# Cing_bot.net
KiCad netlist of a schematic drawn in EAGLE
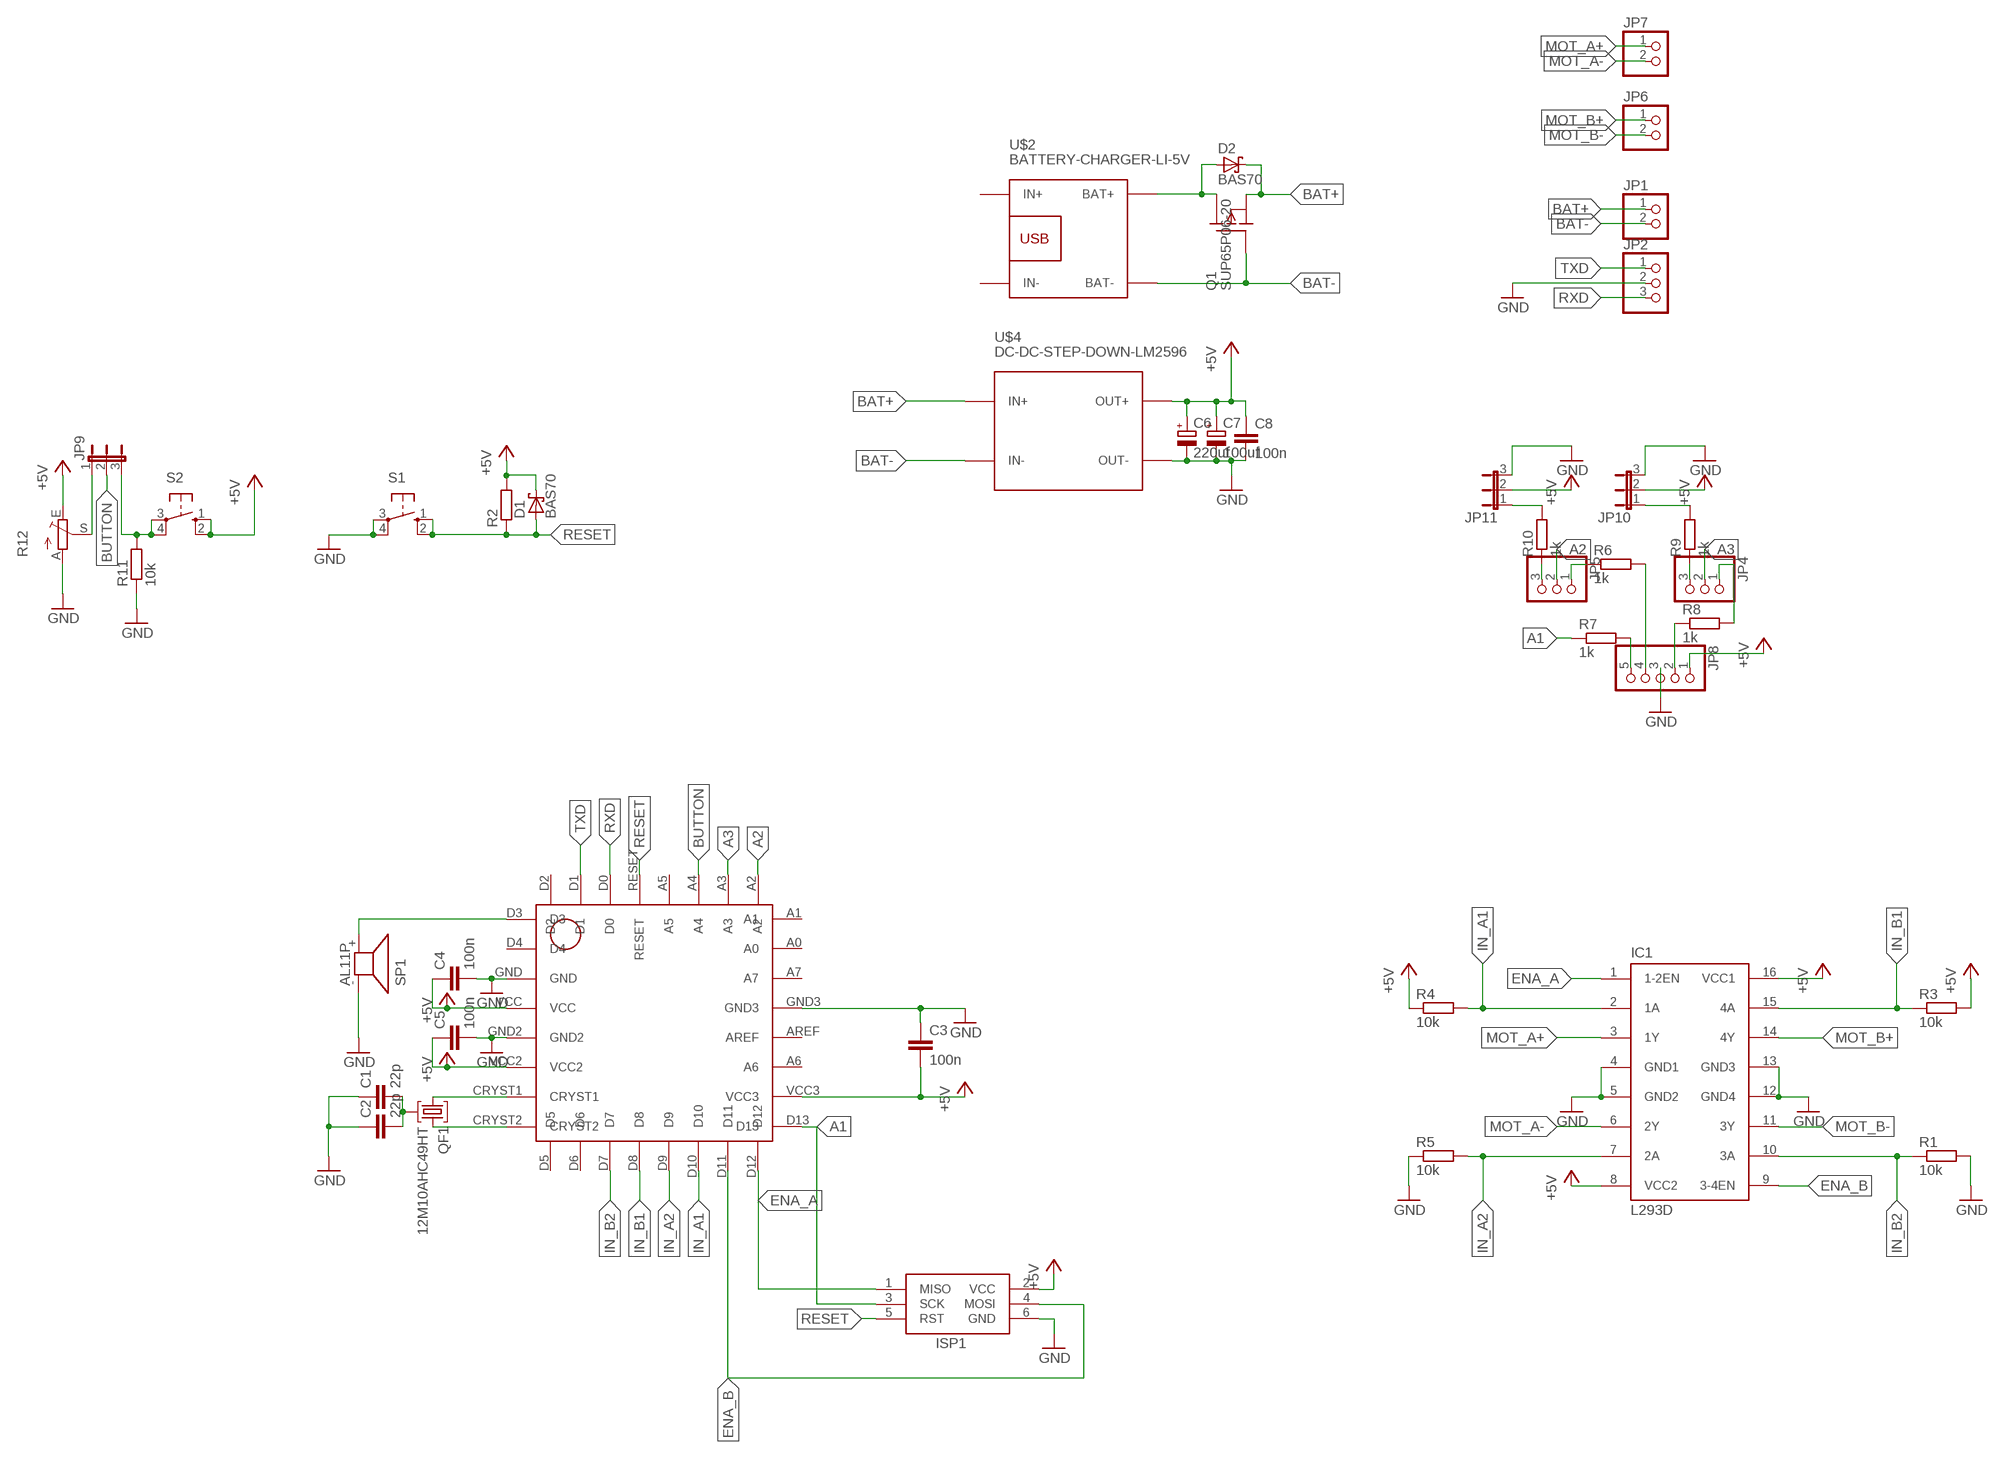
[diagram p0: schematic, sheet 1]

(export (version "E")
  (design (tool "Eeschema 10.0.6"))
  (components
    (comp (ref "C1")
      (value "22p")
      (footprint "eagle-import:C1206")
      (libsource (lib "eagle-import") (part "C-EUC1206"))
    )
    (comp (ref "C2")
      (value "22p")
      (footprint "eagle-import:C1206")
      (libsource (lib "eagle-import") (part "C-EUC1206"))
    )
    (comp (ref "C3")
      (value "100n")
      (footprint "eagle-import:C1206")
      (libsource (lib "eagle-import") (part "C-EUC1206"))
    )
    (comp (ref "C4")
      (value "100n")
      (footprint "eagle-import:C1206")
      (libsource (lib "eagle-import") (part "C-EUC1206"))
    )
    (comp (ref "C5")
      (value "100n")
      (footprint "eagle-import:C1206")
      (libsource (lib "eagle-import") (part "C-EUC1206"))
    )
    (comp (ref "C6")
      (value "220uf")
      (footprint "eagle-import:E3,5-8")
      (libsource (lib "eagle-import") (part "CPOL-EUE3.5-8"))
    )
    (comp (ref "C7")
      (value "100uf")
      (footprint "eagle-import:E3,5-8")
      (libsource (lib "eagle-import") (part "CPOL-EUE3.5-8"))
    )
    (comp (ref "C8")
      (value "100n")
      (footprint "eagle-import:C1206")
      (libsource (lib "eagle-import") (part "C-EUC1206"))
    )
    (comp (ref "D1")
      (value "BAS70")
      (footprint "eagle-import:SOT23")
      (libsource (lib "eagle-import") (part "BAS70"))
    )
    (comp (ref "D2")
      (value "BAS70")
      (footprint "eagle-import:SOT23")
      (libsource (lib "eagle-import") (part "BAS70"))
    )
    (comp (ref "IC1")
      (value "L293D")
      (footprint "eagle-import:DIL16")
      (libsource (lib "eagle-import") (part "L293D"))
    )
    (comp (ref "ISP1")
      (value "AVRISP-6")
      (footprint "eagle-import:AVRISP")
      (libsource (lib "eagle-import") (part "AVRISP-6"))
    )
    (comp (ref "JP1")
      (value "PINHD-1X2")
      (footprint "eagle-import:1X02")
      (libsource (lib "eagle-import") (part "PINHD-1X2"))
    )
    (comp (ref "JP2")
      (value "PINHD-1X3")
      (footprint "eagle-import:1X03")
      (libsource (lib "eagle-import") (part "PINHD-1X3"))
    )
    (comp (ref "JP4")
      (value "PINHD-1X3")
      (footprint "eagle-import:1X03")
      (libsource (lib "eagle-import") (part "PINHD-1X3"))
    )
    (comp (ref "JP5")
      (value "PINHD-1X3")
      (footprint "eagle-import:1X03")
      (libsource (lib "eagle-import") (part "PINHD-1X3"))
    )
    (comp (ref "JP6")
      (value "PINHD-1X2")
      (footprint "eagle-import:1X02")
      (libsource (lib "eagle-import") (part "PINHD-1X2"))
    )
    (comp (ref "JP7")
      (value "PINHD-1X2")
      (footprint "eagle-import:1X02")
      (libsource (lib "eagle-import") (part "PINHD-1X2"))
    )
    (comp (ref "JP8")
      (value "PINHD-1X5")
      (footprint "eagle-import:1X05")
      (libsource (lib "eagle-import") (part "PINHD-1X5"))
    )
    (comp (ref "JP9")
      (value "JP2E")
      (footprint "eagle-import:JP2")
      (libsource (lib "eagle-import") (part "JP2E"))
    )
    (comp (ref "JP10")
      (value "JP2E")
      (footprint "eagle-import:JP2")
      (libsource (lib "eagle-import") (part "JP2E"))
    )
    (comp (ref "JP11")
      (value "JP2E")
      (footprint "eagle-import:JP2")
      (libsource (lib "eagle-import") (part "JP2E"))
    )
    (comp (ref "Q1")
      (value "SUP65P06-20")
      (footprint "eagle-import:TO220")
      (libsource (lib "eagle-import") (part "SUP65P06-20"))
    )
    (comp (ref "QF1")
      (value "12M10AHC49HT")
      (footprint "eagle-import:HC49U")
      (libsource (lib "eagle-import") (part "12M10AHC49HT"))
    )
    (comp (ref "R1")
      (value "10k")
      (footprint "eagle-import:R1206")
      (libsource (lib "eagle-import") (part "R-EU_R1206"))
    )
    (comp (ref "R2")
      (value "R-EU_R1206")
      (footprint "eagle-import:R1206")
      (libsource (lib "eagle-import") (part "R-EU_R1206"))
    )
    (comp (ref "R3")
      (value "10k")
      (footprint "eagle-import:R1206")
      (libsource (lib "eagle-import") (part "R-EU_R1206"))
    )
    (comp (ref "R4")
      (value "10k")
      (footprint "eagle-import:R1206")
      (libsource (lib "eagle-import") (part "R-EU_R1206"))
    )
    (comp (ref "R5")
      (value "10k")
      (footprint "eagle-import:R1206")
      (libsource (lib "eagle-import") (part "R-EU_R1206"))
    )
    (comp (ref "R6")
      (value "1k")
      (footprint "eagle-import:R1206")
      (libsource (lib "eagle-import") (part "R-EU_R1206"))
    )
    (comp (ref "R7")
      (value "1k")
      (footprint "eagle-import:R1206")
      (libsource (lib "eagle-import") (part "R-EU_R1206"))
    )
    (comp (ref "R8")
      (value "1k")
      (footprint "eagle-import:R1206")
      (libsource (lib "eagle-import") (part "R-EU_R1206"))
    )
    (comp (ref "R9")
      (value "1k")
      (footprint "eagle-import:R1206")
      (libsource (lib "eagle-import") (part "R-EU_R1206"))
    )
    (comp (ref "R10")
      (value "1k")
      (footprint "eagle-import:R1206")
      (libsource (lib "eagle-import") (part "R-EU_R1206"))
    )
    (comp (ref "R11")
      (value "10k")
      (footprint "eagle-import:R1206")
      (libsource (lib "eagle-import") (part "R-EU_R1206"))
    )
    (comp (ref "R12")
      (value "TRIM_EU-CA6V")
      (footprint "eagle-import:CA6V")
      (libsource (lib "eagle-import") (part "TRIM_EU-CA6V"))
    )
    (comp (ref "S1")
      (value "10-XX")
      (footprint "eagle-import:B3F-10XX")
      (fields (field (name "MPN") "B3F-1000"))
      (libsource (lib "eagle-import") (part "10-XX"))
    )
    (comp (ref "S2")
      (value "10-XX")
      (footprint "eagle-import:B3F-10XX")
      (fields (field (name "MPN") "B3F-1000"))
      (libsource (lib "eagle-import") (part "10-XX"))
    )
    (comp (ref "SP1")
      (value "AL11P")
      (footprint "eagle-import:AL11P")
      (libsource (lib "eagle-import") (part "AL11P"))
    )
    (comp (ref "U$1")
      (value "PROCESSOR")
      (footprint "eagle-import:PROCESOR")
      (libsource (lib "eagle-import") (part "PROCESSOR"))
    )
    (comp (ref "U$2")
      (value "BATTERY-CHARGER-LI-5V")
      (footprint "eagle-import:BATTERY-CHARGER-LI-5V")
      (libsource (lib "eagle-import") (part "BATTERY-CHARGER-LI-5V"))
    )
    (comp (ref "U$4")
      (value "DC-DC-STEP-DOWN-LM2596")
      (footprint "eagle-import:DC-DC-STEP-DOWN-LM2596")
      (libsource (lib "eagle-import") (part "DC-DC-STEP-DOWN-LM2596"))
    )
  )
  (nets
    (net (code "1") (name "+5V") (class "Default")
      (node (ref "C3") (pin "2") (pinfunction "2_2") (pintype "passive"))
      (node (ref "C4") (pin "1") (pinfunction "1_1") (pintype "passive"))
      (node (ref "C5") (pin "1") (pinfunction "1_1") (pintype "passive"))
      (node (ref "C6") (pin "+") (pinfunction "+_+") (pintype "passive"))
      (node (ref "C7") (pin "+") (pinfunction "+_+") (pintype "passive"))
      (node (ref "C8") (pin "1") (pinfunction "1_1") (pintype "passive"))
      (node (ref "D1") (pin "3") (pinfunction "C_3") (pintype "passive"))
      (node (ref "IC1") (pin "16") (pinfunction "VCC1_16") (pintype "power_in"))
      (node (ref "IC1") (pin "8") (pinfunction "VCC2_8") (pintype "power_in"))
      (node (ref "ISP1") (pin "2") (pinfunction "VCC_2") (pintype "power_in"))
      (node (ref "JP10") (pin "2") (pinfunction "2_2") (pintype "passive"))
      (node (ref "JP11") (pin "2") (pinfunction "2_2") (pintype "passive"))
      (node (ref "JP8") (pin "1") (pinfunction "1_1") (pintype "passive"))
      (node (ref "R12") (pin "E") (pinfunction "E_E") (pintype "passive"))
      (node (ref "R2") (pin "2") (pinfunction "2_2") (pintype "passive"))
      (node (ref "R3") (pin "2") (pinfunction "2_2") (pintype "passive"))
      (node (ref "R4") (pin "1") (pinfunction "1_1") (pintype "passive"))
      (node (ref "S2") (pin "1") (pinfunction "S_1") (pintype "passive"))
      (node (ref "S2") (pin "2") (pinfunction "S1_2") (pintype "passive"))
      (node (ref "U$1") (pin "VCC") (pinfunction "VCC_VCC") (pintype "bidirectional"))
      (node (ref "U$1") (pin "VCC2") (pinfunction "VCC2_VCC2") (pintype "bidirectional"))
      (node (ref "U$1") (pin "VCC3") (pinfunction "VCC3_VCC3") (pintype "bidirectional"))
      (node (ref "U$4") (pin "OUT+") (pinfunction "OUT+_OUT+") (pintype "bidirectional"))
    )
    (net (code "2") (name "A1") (class "Default")
      (node (ref "ISP1") (pin "3") (pinfunction "SCK_3") (pintype "output"))
      (node (ref "R7") (pin "1") (pinfunction "1_1") (pintype "passive"))
      (node (ref "U$1") (pin "D13") (pinfunction "D13_D13") (pintype "bidirectional"))
    )
    (net (code "3") (name "A2") (class "Default")
      (node (ref "JP5") (pin "2") (pinfunction "2_2") (pintype "passive"))
      (node (ref "U$1") (pin "A2") (pinfunction "A2_A2") (pintype "bidirectional"))
    )
    (net (code "4") (name "A3") (class "Default")
      (node (ref "JP4") (pin "2") (pinfunction "2_2") (pintype "passive"))
      (node (ref "U$1") (pin "A3") (pinfunction "A3_A3") (pintype "bidirectional"))
    )
    (net (code "5") (name "BAT+") (class "Default")
      (node (ref "D2") (pin "3") (pinfunction "C_3") (pintype "passive"))
      (node (ref "JP1") (pin "1") (pinfunction "1_1") (pintype "passive"))
      (node (ref "Q1") (pin "3") (pinfunction "S_3") (pintype "passive"))
      (node (ref "U$4") (pin "IN+") (pinfunction "IN+_IN+") (pintype "bidirectional"))
    )
    (net (code "6") (name "BAT-") (class "Default")
      (node (ref "JP1") (pin "2") (pinfunction "2_2") (pintype "passive"))
      (node (ref "Q1") (pin "1") (pinfunction "G_1") (pintype "passive"))
      (node (ref "U$2") (pin "BAT-") (pinfunction "BAT-_BAT-") (pintype "bidirectional"))
      (node (ref "U$4") (pin "IN-") (pinfunction "IN-_IN-") (pintype "bidirectional"))
    )
    (net (code "7") (name "BUTTON") (class "Default")
      (node (ref "JP9") (pin "2") (pinfunction "2_2") (pintype "passive"))
      (node (ref "U$1") (pin "A4") (pinfunction "A4_A4") (pintype "bidirectional"))
    )
    (net (code "8") (name "ENA_A") (class "Default")
      (node (ref "IC1") (pin "1") (pinfunction "1-2EN_1") (pintype "input"))
      (node (ref "ISP1") (pin "1") (pinfunction "MISO_1") (pintype "input"))
      (node (ref "U$1") (pin "D12") (pinfunction "D12_D12") (pintype "bidirectional"))
    )
    (net (code "9") (name "ENA_B") (class "Default")
      (node (ref "IC1") (pin "9") (pinfunction "3-4EN_9") (pintype "input"))
      (node (ref "ISP1") (pin "4") (pinfunction "MOSI_4") (pintype "output"))
      (node (ref "U$1") (pin "D11") (pinfunction "D11_D11") (pintype "bidirectional"))
    )
    (net (code "10") (name "GND") (class "Default")
      (node (ref "C1") (pin "1") (pinfunction "1_1") (pintype "passive"))
      (node (ref "C2") (pin "1") (pinfunction "1_1") (pintype "passive"))
      (node (ref "C3") (pin "1") (pinfunction "1_1") (pintype "passive"))
      (node (ref "C4") (pin "2") (pinfunction "2_2") (pintype "passive"))
      (node (ref "C5") (pin "2") (pinfunction "2_2") (pintype "passive"))
      (node (ref "C6") (pin "-") (pinfunction "-_-") (pintype "passive"))
      (node (ref "C7") (pin "-") (pinfunction "-_-") (pintype "passive"))
      (node (ref "C8") (pin "2") (pinfunction "2_2") (pintype "passive"))
      (node (ref "IC1") (pin "12") (pinfunction "GND4_12") (pintype "power_in"))
      (node (ref "IC1") (pin "13") (pinfunction "GND3_13") (pintype "power_in"))
      (node (ref "IC1") (pin "4") (pinfunction "GND1_4") (pintype "power_in"))
      (node (ref "IC1") (pin "5") (pinfunction "GND2_5") (pintype "power_in"))
      (node (ref "ISP1") (pin "6") (pinfunction "GND_6") (pintype "power_in"))
      (node (ref "JP10") (pin "3") (pinfunction "3_3") (pintype "passive"))
      (node (ref "JP11") (pin "3") (pinfunction "3_3") (pintype "passive"))
      (node (ref "JP2") (pin "2") (pinfunction "2_2") (pintype "passive"))
      (node (ref "JP8") (pin "3") (pinfunction "3_3") (pintype "passive"))
      (node (ref "R1") (pin "2") (pinfunction "2_2") (pintype "passive"))
      (node (ref "R11") (pin "1") (pinfunction "1_1") (pintype "passive"))
      (node (ref "R12") (pin "A") (pinfunction "A_A") (pintype "passive"))
      (node (ref "R5") (pin "1") (pinfunction "1_1") (pintype "passive"))
      (node (ref "S1") (pin "3") (pinfunction "P_3") (pintype "passive"))
      (node (ref "S1") (pin "4") (pinfunction "P1_4") (pintype "passive"))
      (node (ref "SP1") (pin "-") (pinfunction "1_-") (pintype "passive"))
      (node (ref "U$1") (pin "GND") (pinfunction "GND_GND") (pintype "bidirectional"))
      (node (ref "U$1") (pin "GND2") (pinfunction "GND2_GND2") (pintype "bidirectional"))
      (node (ref "U$1") (pin "GND3") (pinfunction "GND3_GND3") (pintype "bidirectional"))
      (node (ref "U$4") (pin "OUT-") (pinfunction "OUT-_OUT-") (pintype "bidirectional"))
    )
    (net (code "11") (name "IN_A1") (class "Default")
      (node (ref "IC1") (pin "2") (pinfunction "1A_2") (pintype "input"))
      (node (ref "R4") (pin "2") (pinfunction "2_2") (pintype "passive"))
      (node (ref "U$1") (pin "D10") (pinfunction "D10_D10") (pintype "bidirectional"))
    )
    (net (code "12") (name "IN_A2") (class "Default")
      (node (ref "IC1") (pin "7") (pinfunction "2A_7") (pintype "input"))
      (node (ref "R5") (pin "2") (pinfunction "2_2") (pintype "passive"))
      (node (ref "U$1") (pin "D9") (pinfunction "D9_D9") (pintype "bidirectional"))
    )
    (net (code "13") (name "IN_B1") (class "Default")
      (node (ref "IC1") (pin "15") (pinfunction "4A_15") (pintype "input"))
      (node (ref "R3") (pin "1") (pinfunction "1_1") (pintype "passive"))
      (node (ref "U$1") (pin "D8") (pinfunction "D8_D8") (pintype "bidirectional"))
    )
    (net (code "14") (name "IN_B2") (class "Default")
      (node (ref "IC1") (pin "10") (pinfunction "3A_10") (pintype "input"))
      (node (ref "R1") (pin "1") (pinfunction "1_1") (pintype "passive"))
      (node (ref "U$1") (pin "D7") (pinfunction "D7_D7") (pintype "bidirectional"))
    )
    (net (code "15") (name "MOT_A+") (class "Default")
      (node (ref "IC1") (pin "3") (pinfunction "1Y_3") (pintype "output"))
      (node (ref "JP7") (pin "1") (pinfunction "1_1") (pintype "passive"))
    )
    (net (code "16") (name "MOT_A-") (class "Default")
      (node (ref "IC1") (pin "6") (pinfunction "2Y_6") (pintype "output"))
      (node (ref "JP7") (pin "2") (pinfunction "2_2") (pintype "passive"))
    )
    (net (code "17") (name "MOT_B+") (class "Default")
      (node (ref "IC1") (pin "14") (pinfunction "4Y_14") (pintype "output"))
      (node (ref "JP6") (pin "1") (pinfunction "1_1") (pintype "passive"))
    )
    (net (code "18") (name "MOT_B-") (class "Default")
      (node (ref "IC1") (pin "11") (pinfunction "3Y_11") (pintype "output"))
      (node (ref "JP6") (pin "2") (pinfunction "2_2") (pintype "passive"))
    )
    (net (code "19") (name "Net-(C1-Pad2)") (class "Default")
      (node (ref "C1") (pin "2") (pinfunction "2_2") (pintype "passive"))
      (node (ref "C2") (pin "2") (pinfunction "2_2") (pintype "passive"))
      (node (ref "QF1") (pin "2") (pinfunction "2_2") (pintype "passive"))
    )
    (net (code "20") (name "Net-(D2-A)") (class "Default")
      (node (ref "D2") (pin "1") (pinfunction "A_1") (pintype "passive"))
      (node (ref "Q1") (pin "2") (pinfunction "D_2") (pintype "passive"))
      (node (ref "U$2") (pin "BAT+") (pinfunction "BAT+_BAT+") (pintype "bidirectional"))
    )
    (net (code "21") (name "Net-(JP4-Pad1)") (class "Default")
      (node (ref "JP4") (pin "1") (pinfunction "1_1") (pintype "passive"))
      (node (ref "R8") (pin "2") (pinfunction "2_2") (pintype "passive"))
    )
    (net (code "22") (name "Net-(JP4-Pad3)") (class "Default")
      (node (ref "JP4") (pin "3") (pinfunction "3_3") (pintype "passive"))
      (node (ref "R9") (pin "1") (pinfunction "1_1") (pintype "passive"))
    )
    (net (code "23") (name "Net-(JP5-Pad1)") (class "Default")
      (node (ref "JP5") (pin "1") (pinfunction "1_1") (pintype "passive"))
      (node (ref "R6") (pin "1") (pinfunction "1_1") (pintype "passive"))
    )
    (net (code "24") (name "Net-(JP5-Pad3)") (class "Default")
      (node (ref "JP5") (pin "3") (pinfunction "3_3") (pintype "passive"))
      (node (ref "R10") (pin "1") (pinfunction "1_1") (pintype "passive"))
    )
    (net (code "25") (name "Net-(JP8-Pad2)") (class "Default")
      (node (ref "JP8") (pin "2") (pinfunction "2_2") (pintype "passive"))
      (node (ref "R8") (pin "1") (pinfunction "1_1") (pintype "passive"))
    )
    (net (code "26") (name "Net-(JP8-Pad4)") (class "Default")
      (node (ref "JP8") (pin "4") (pinfunction "4_4") (pintype "passive"))
      (node (ref "R6") (pin "2") (pinfunction "2_2") (pintype "passive"))
    )
    (net (code "27") (name "Net-(JP8-Pad5)") (class "Default")
      (node (ref "JP8") (pin "5") (pinfunction "5_5") (pintype "passive"))
      (node (ref "R7") (pin "2") (pinfunction "2_2") (pintype "passive"))
    )
    (net (code "28") (name "Net-(JP9-Pad1)") (class "Default")
      (node (ref "JP9") (pin "1") (pinfunction "1_1") (pintype "passive"))
      (node (ref "R12") (pin "S") (pinfunction "S_S") (pintype "passive"))
    )
    (net (code "29") (name "Net-(JP10-Pad1)") (class "Default")
      (node (ref "JP10") (pin "1") (pinfunction "1_1") (pintype "passive"))
      (node (ref "R9") (pin "2") (pinfunction "2_2") (pintype "passive"))
    )
    (net (code "30") (name "Net-(JP11-Pad1)") (class "Default")
      (node (ref "JP11") (pin "1") (pinfunction "1_1") (pintype "passive"))
      (node (ref "R10") (pin "2") (pinfunction "2_2") (pintype "passive"))
    )
    (net (code "31") (name "Net-(QF1-Pad1)") (class "Default")
      (node (ref "QF1") (pin "1") (pinfunction "1_1") (pintype "passive"))
      (node (ref "U$1") (pin "CRYST1") (pinfunction "CRYST1_CRYST1") (pintype "bidirectional"))
    )
    (net (code "32") (name "Net-(QF1-Pad3)") (class "Default")
      (node (ref "QF1") (pin "3") (pinfunction "3_3") (pintype "passive"))
      (node (ref "U$1") (pin "CRYST2") (pinfunction "CRYST2_CRYST2") (pintype "bidirectional"))
    )
    (net (code "33") (name "Net-(S2-P)") (class "Default")
      (node (ref "JP9") (pin "3") (pinfunction "3_3") (pintype "passive"))
      (node (ref "R11") (pin "2") (pinfunction "2_2") (pintype "passive"))
      (node (ref "S2") (pin "3") (pinfunction "P_3") (pintype "passive"))
      (node (ref "S2") (pin "4") (pinfunction "P1_4") (pintype "passive"))
    )
    (net (code "34") (name "Net-(SP1-2)") (class "Default")
      (node (ref "SP1") (pin "+") (pinfunction "2_+") (pintype "passive"))
      (node (ref "U$1") (pin "D3") (pinfunction "D3_D3") (pintype "bidirectional"))
    )
    (net (code "35") (name "RESET") (class "Default")
      (node (ref "D1") (pin "1") (pinfunction "A_1") (pintype "passive"))
      (node (ref "ISP1") (pin "5") (pinfunction "RST_5") (pintype "output"))
      (node (ref "R2") (pin "1") (pinfunction "1_1") (pintype "passive"))
      (node (ref "S1") (pin "1") (pinfunction "S_1") (pintype "passive"))
      (node (ref "S1") (pin "2") (pinfunction "S1_2") (pintype "passive"))
      (node (ref "U$1") (pin "RESET") (pinfunction "RESET_RESET") (pintype "bidirectional"))
    )
    (net (code "36") (name "RXD") (class "Default")
      (node (ref "JP2") (pin "3") (pinfunction "3_3") (pintype "passive"))
      (node (ref "U$1") (pin "D0") (pinfunction "D0_D0") (pintype "bidirectional"))
    )
    (net (code "37") (name "TXD") (class "Default")
      (node (ref "JP2") (pin "1") (pinfunction "1_1") (pintype "passive"))
      (node (ref "U$1") (pin "D1") (pinfunction "D1_D1") (pintype "bidirectional"))
    )
    (net (code "38") (name "unconnected-(U$1-PadA0)") (class "Default")
      (node (ref "U$1") (pin "A0") (pinfunction "A0_A0") (pintype "bidirectional"))
    )
    (net (code "39") (name "unconnected-(U$1-PadA1)") (class "Default")
      (node (ref "U$1") (pin "A1") (pinfunction "A1_A1") (pintype "bidirectional"))
    )
    (net (code "40") (name "unconnected-(U$1-PadA5)") (class "Default")
      (node (ref "U$1") (pin "A5") (pinfunction "A5_A5") (pintype "bidirectional"))
    )
    (net (code "41") (name "unconnected-(U$1-PadA6)") (class "Default")
      (node (ref "U$1") (pin "A6") (pinfunction "A6_A6") (pintype "bidirectional"))
    )
    (net (code "42") (name "unconnected-(U$1-PadA7)") (class "Default")
      (node (ref "U$1") (pin "A7") (pinfunction "A7_A7") (pintype "bidirectional"))
    )
    (net (code "43") (name "unconnected-(U$1-PadAREF)") (class "Default")
      (node (ref "U$1") (pin "AREF") (pinfunction "AREF_AREF") (pintype "bidirectional"))
    )
    (net (code "44") (name "unconnected-(U$1-PadD2)") (class "Default")
      (node (ref "U$1") (pin "D2") (pinfunction "D2_D2") (pintype "bidirectional"))
    )
    (net (code "45") (name "unconnected-(U$1-PadD4)") (class "Default")
      (node (ref "U$1") (pin "D4") (pinfunction "D4_D4") (pintype "bidirectional"))
    )
    (net (code "46") (name "unconnected-(U$1-PadD5)") (class "Default")
      (node (ref "U$1") (pin "D5") (pinfunction "D5_D5") (pintype "bidirectional"))
    )
    (net (code "47") (name "unconnected-(U$1-PadD6)") (class "Default")
      (node (ref "U$1") (pin "D6") (pinfunction "D6_D6") (pintype "bidirectional"))
    )
    (net (code "48") (name "unconnected-(U$2-PadIN+)") (class "Default")
      (node (ref "U$2") (pin "IN+") (pinfunction "IN+_IN+") (pintype "bidirectional"))
    )
    (net (code "49") (name "unconnected-(U$2-PadIN-)") (class "Default")
      (node (ref "U$2") (pin "IN-") (pinfunction "IN-_IN-") (pintype "bidirectional"))
    )
  )
)
